# nixie_clock.net
KiCad netlist of a schematic drawn in EAGLE
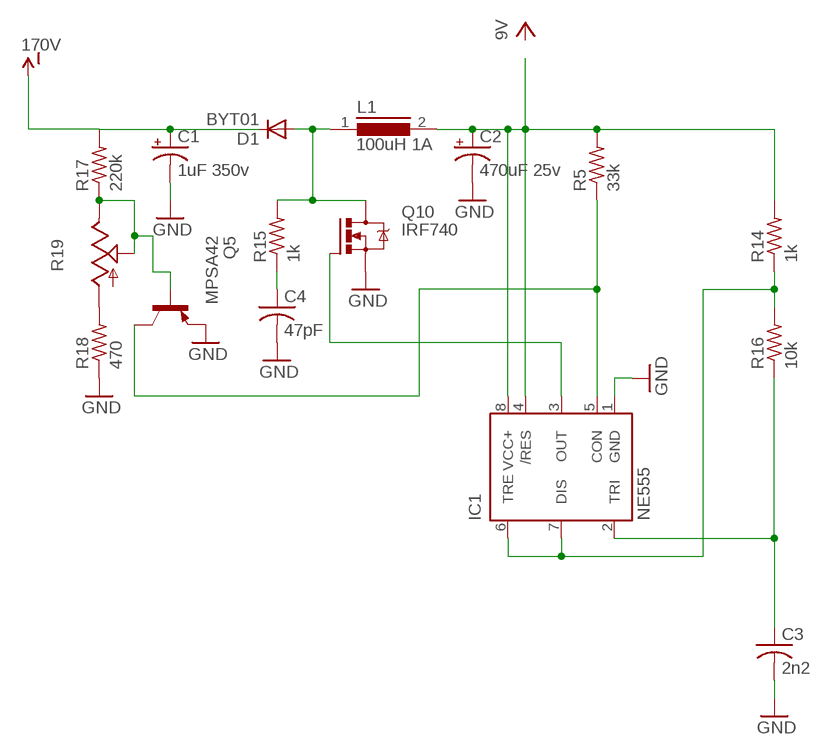
[diagram p0: schematic, sheet 2]

(export (version "E")
  (design (tool "Eeschema 10.0.6"))
  (components
    (comp (ref "C1")
      (value "1uF 350v")
      (footprint "eagle-import:E2,5-7")
      (libsource (lib "eagle-import") (part "CPOL-USE2.5-7"))
    )
    (comp (ref "C2")
      (value "470uF 25v")
      (footprint "eagle-import:E5-10,5")
      (libsource (lib "eagle-import") (part "CPOL-USE5-10.5"))
    )
    (comp (ref "C3")
      (value "2n2")
      (footprint "eagle-import:C050-024X044")
      (libsource (lib "eagle-import") (part "C-US050-024X044"))
    )
    (comp (ref "C4")
      (value "47pF")
      (footprint "eagle-import:C075-032X103")
      (libsource (lib "eagle-import") (part "C-US075-032X103"))
    )
    (comp (ref "D1")
      (value "BYT01")
      (footprint "eagle-import:F126-10")
      (libsource (lib "eagle-import") (part "BYT01"))
    )
    (comp (ref "IC1")
      (value "NE555")
      (footprint "eagle-import:DIL-08")
      (libsource (lib "eagle-import") (part "NE555"))
    )
    (comp (ref "L1")
      (value "100uH 1A")
      (footprint "eagle-import:MESC26")
      (libsource (lib "eagle-import") (part "MESC26"))
    )
    (comp (ref "Q5")
      (value "MPSA42")
      (footprint "eagle-import:TO92-CBE")
      (libsource (lib "eagle-import") (part "2N4126"))
    )
    (comp (ref "Q10")
      (value "IRF740")
      (footprint "eagle-import:TO220BV")
      (libsource (lib "eagle-import") (part "IRF740"))
    )
    (comp (ref "R5")
      (value "33k")
      (footprint "eagle-import:0207_2V")
      (libsource (lib "eagle-import") (part "R-US_0207/2V"))
    )
    (comp (ref "R14")
      (value "1k")
      (footprint "eagle-import:0207_2V")
      (libsource (lib "eagle-import") (part "R-US_0207/2V"))
    )
    (comp (ref "R15")
      (value "1k")
      (footprint "eagle-import:0207_2V")
      (libsource (lib "eagle-import") (part "R-US_0207/2V"))
    )
    (comp (ref "R16")
      (value "10k")
      (footprint "eagle-import:0207_2V")
      (libsource (lib "eagle-import") (part "R-US_0207/2V"))
    )
    (comp (ref "R17")
      (value "220k")
      (footprint "eagle-import:0207_2V")
      (libsource (lib "eagle-import") (part "R-US_0207/2V"))
    )
    (comp (ref "R18")
      (value "470")
      (footprint "eagle-import:0207_2V")
      (libsource (lib "eagle-import") (part "R-US_0207/2V"))
    )
    (comp (ref "R19")
      (value "TRIM_US-B25P")
      (footprint "eagle-import:B25P")
      (libsource (lib "eagle-import") (part "TRIM_US-B25P"))
    )
  )
  (nets
    (net (code "2") (name "170V") (class "Default")
      (node (ref "C1") (pin "+") (pinfunction "+_+") (pintype "passive"))
      (node (ref "D1") (pin "C") (pinfunction "C_C") (pintype "passive"))
      (node (ref "R17") (pin "2") (pinfunction "2_2") (pintype "passive"))
    )
    (net (code "3") (name "GND") (class "Default")
      (node (ref "C1") (pin "-") (pinfunction "-_-") (pintype "passive"))
      (node (ref "C2") (pin "-") (pinfunction "-_-") (pintype "passive"))
      (node (ref "C3") (pin "2") (pinfunction "2_2") (pintype "passive"))
      (node (ref "C4") (pin "2") (pinfunction "2_2") (pintype "passive"))
      (node (ref "IC1") (pin "1") (pinfunction "GND_1") (pintype "power_in"))
      (node (ref "Q10") (pin "S") (pinfunction "S_S") (pintype "passive"))
      (node (ref "Q5") (pin "E") (pinfunction "E_E") (pintype "passive"))
      (node (ref "R18") (pin "1") (pinfunction "1_1") (pintype "passive"))
    )
    (net (code "4") (name "Net-(C4-Pad1)") (class "Default")
      (node (ref "C4") (pin "1") (pinfunction "1_1") (pintype "passive"))
      (node (ref "R15") (pin "1") (pinfunction "1_1") (pintype "passive"))
    )
    (net (code "5") (name "Net-(D1-PadA)") (class "Default")
      (node (ref "D1") (pin "A") (pinfunction "A_A") (pintype "passive"))
      (node (ref "L1") (pin "1") (pinfunction "1_1") (pintype "passive"))
      (node (ref "Q10") (pin "D") (pinfunction "D_D") (pintype "passive"))
      (node (ref "R15") (pin "2") (pinfunction "2_2") (pintype "passive"))
    )
    (net (code "6") (name "Net-(IC1-CON)") (class "Default")
      (node (ref "IC1") (pin "5") (pinfunction "CON_5") (pintype "input"))
      (node (ref "Q5") (pin "C") (pinfunction "C_C") (pintype "passive"))
      (node (ref "R5") (pin "1") (pinfunction "1_1") (pintype "passive"))
    )
    (net (code "7") (name "Net-(IC1-DIS)") (class "Default")
      (node (ref "IC1") (pin "6") (pinfunction "TRE_6") (pintype "input"))
      (node (ref "IC1") (pin "7") (pinfunction "DIS_7") (pintype "input"))
      (node (ref "R14") (pin "1") (pinfunction "1_1") (pintype "passive"))
      (node (ref "R16") (pin "2") (pinfunction "2_2") (pintype "passive"))
    )
    (net (code "8") (name "Net-(IC1-OUT)") (class "Default")
      (node (ref "IC1") (pin "3") (pinfunction "OUT_3") (pintype "output"))
      (node (ref "Q10") (pin "G") (pinfunction "G_G") (pintype "passive"))
    )
    (net (code "9") (name "Net-(IC1-TRI)") (class "Default")
      (node (ref "C3") (pin "1") (pinfunction "1_1") (pintype "passive"))
      (node (ref "IC1") (pin "2") (pinfunction "TRI_2") (pintype "input"))
      (node (ref "R16") (pin "1") (pinfunction "1_1") (pintype "passive"))
    )
    (net (code "10") (name "Net-(IC1-VCC+)") (class "Default")
      (node (ref "C2") (pin "+") (pinfunction "+_+") (pintype "passive"))
      (node (ref "IC1") (pin "4") (pinfunction "/RES_4") (pintype "input"))
      (node (ref "IC1") (pin "8") (pinfunction "VCC+_8") (pintype "power_in"))
      (node (ref "L1") (pin "2") (pinfunction "2_2") (pintype "passive"))
      (node (ref "R14") (pin "2") (pinfunction "2_2") (pintype "passive"))
      (node (ref "R5") (pin "2") (pinfunction "2_2") (pintype "passive"))
    )
    (net (code "11") (name "Net-(Q5-PadB)") (class "Default")
      (node (ref "Q5") (pin "B") (pinfunction "B_B") (pintype "passive"))
      (node (ref "R17") (pin "1") (pinfunction "1_1") (pintype "passive"))
      (node (ref "R19") (pin "E") (pinfunction "E_E") (pintype "passive"))
      (node (ref "R19") (pin "S") (pinfunction "S_S") (pintype "passive"))
    )
    (net (code "12") (name "Net-(R18-Pad2)") (class "Default")
      (node (ref "R18") (pin "2") (pinfunction "2_2") (pintype "passive"))
      (node (ref "R19") (pin "A") (pinfunction "A_A") (pintype "passive"))
    )
  )
)
